# AudioPreAmp-LM741.net
KiCad netlist of a schematic drawn in EAGLE
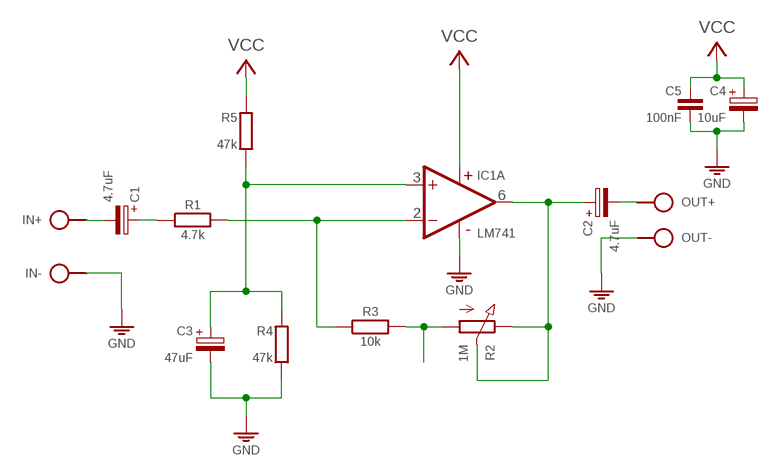
[diagram p0: schematic, sheet 1]

(export (version "E")
  (design (tool "Eeschema 10.0.6"))
  (components
    (comp (ref "C1")
      (value "4.7uF")
      (footprint "eagle-import:E2.5-4_V")
      (libsource (lib "eagle-import") (part "CPOLE2,5-4/V"))
    )
    (comp (ref "C2")
      (value "4.7uF")
      (footprint "eagle-import:E2,5-4")
      (libsource (lib "eagle-import") (part "CPOLE2,5-4"))
    )
    (comp (ref "C3")
      (value "47uF")
      (footprint "eagle-import:E2,5-4")
      (libsource (lib "eagle-import") (part "CPOLE2,5-4"))
    )
    (comp (ref "C4")
      (value "10uF")
      (footprint "eagle-import:E2,5-4")
      (libsource (lib "eagle-import") (part "CPOLE2,5-4"))
    )
    (comp (ref "C5")
      (value "100nF")
      (footprint "eagle-import:C050-020X044_V")
      (libsource (lib "eagle-import") (part "C050-020X044/V"))
    )
    (comp (ref "IC1")
      (value "LM741")
      (footprint "eagle-import:DIL08")
      (libsource (lib "eagle-import") (part "LM741"))
    )
    (comp (ref "IN")
      (value "SPAD+--+")
      (footprint "eagle-import:SPAD-+")
      (libsource (lib "eagle-import") (part "SPAD+--+"))
    )
    (comp (ref "OUT")
      (value "SPAD+-+-")
      (footprint "eagle-import:SPAD+-")
      (libsource (lib "eagle-import") (part "SPAD+-+-"))
    )
    (comp (ref "PWR")
      (value "VCC_GNDL")
      (footprint "eagle-import:SPAD-+")
      (libsource (lib "eagle-import") (part "VCC_GNDL"))
    )
    (comp (ref "R1")
      (value "4.7k")
      (footprint "eagle-import:0204_10")
      (libsource (lib "eagle-import") (part "R-H0204/10"))
    )
    (comp (ref "R2")
      (value "1M")
      (footprint "eagle-import:POT-P5")
      (libsource (lib "eagle-import") (part "POT-P5"))
    )
    (comp (ref "R3")
      (value "10k")
      (footprint "eagle-import:0204_10-V")
      (libsource (lib "eagle-import") (part "R-H0204/10-V"))
    )
    (comp (ref "R4")
      (value "47k")
      (footprint "eagle-import:0204_10-V")
      (libsource (lib "eagle-import") (part "R0204/10-V"))
    )
    (comp (ref "R5")
      (value "47k")
      (footprint "eagle-import:0204_10")
      (libsource (lib "eagle-import") (part "R0204/10"))
    )
  )
  (nets
    (net (code "1") (name "GND") (class "Default")
      (node (ref "C3") (pin "-") (pinfunction "-_-") (pintype "passive"))
      (node (ref "C4") (pin "-") (pinfunction "-_-") (pintype "passive"))
      (node (ref "C5") (pin "2") (pinfunction "2_2") (pintype "passive"))
      (node (ref "IC1") (pin "4") (pinfunction "V-_4") (pintype "power_in"))
      (node (ref "IN") (pin "1") (pinfunction "P$1_1") (pintype "passive"))
      (node (ref "OUT") (pin "1") (pinfunction "P$1_1") (pintype "passive"))
      (node (ref "PWR") (pin "1") (pinfunction "GND_1") (pintype "power_in"))
      (node (ref "R4") (pin "2") (pinfunction "2_2") (pintype "passive"))
    )
    (net (code "2") (name "Net-(C1-Pad+)") (class "Default")
      (node (ref "C1") (pin "+") (pinfunction "+_+") (pintype "passive"))
      (node (ref "R1") (pin "1") (pinfunction "1_1") (pintype "passive"))
    )
    (net (code "3") (name "Net-(IC1A-+IN)") (class "Default")
      (node (ref "C3") (pin "+") (pinfunction "+_+") (pintype "passive"))
      (node (ref "IC1") (pin "3") (pinfunction "+IN_3") (pintype "input"))
      (node (ref "R4") (pin "1") (pinfunction "1_1") (pintype "passive"))
      (node (ref "R5") (pin "1") (pinfunction "2_1") (pintype "passive"))
    )
    (net (code "4") (name "Net-(IC1A--IN)") (class "Default")
      (node (ref "IC1") (pin "2") (pinfunction "-IN_2") (pintype "input"))
      (node (ref "R1") (pin "2") (pinfunction "2_2") (pintype "passive"))
      (node (ref "R3") (pin "1") (pinfunction "1_1") (pintype "passive"))
    )
    (net (code "5") (name "Net-(IC1A-OUT)") (class "Default")
      (node (ref "C2") (pin "+") (pinfunction "+_+") (pintype "passive"))
      (node (ref "IC1") (pin "6") (pinfunction "OUT_6") (pintype "output"))
      (node (ref "R2") (pin "E") (pinfunction "E_E") (pintype "passive"))
      (node (ref "R2") (pin "S") (pinfunction "S_S") (pintype "passive"))
    )
    (net (code "6") (name "Net-(INA-P$1)") (class "Default")
      (node (ref "C1") (pin "-") (pinfunction "-_-") (pintype "passive"))
      (node (ref "IN") (pin "2") (pinfunction "P$1_2") (pintype "passive"))
    )
    (net (code "7") (name "Net-(OUTA-P$1)") (class "Default")
      (node (ref "C2") (pin "-") (pinfunction "-_-") (pintype "passive"))
      (node (ref "OUT") (pin "2") (pinfunction "P$1_2") (pintype "passive"))
    )
    (net (code "8") (name "Net-(R2-PadA)") (class "Default")
      (node (ref "R2") (pin "A") (pinfunction "A_A") (pintype "passive"))
      (node (ref "R3") (pin "2") (pinfunction "2_2") (pintype "passive"))
    )
    (net (code "9") (name "VCC") (class "Default")
      (node (ref "C4") (pin "+") (pinfunction "+_+") (pintype "passive"))
      (node (ref "C5") (pin "1") (pinfunction "1_1") (pintype "passive"))
      (node (ref "IC1") (pin "7") (pinfunction "V+_7") (pintype "power_in"))
      (node (ref "PWR") (pin "2") (pinfunction "VCC_2") (pintype "power_in"))
      (node (ref "R5") (pin "2") (pinfunction "1_2") (pintype "passive"))
    )
  )
)
